# 04_DigitalSensors.net
KiCad netlist of a schematic drawn in Altium Designer
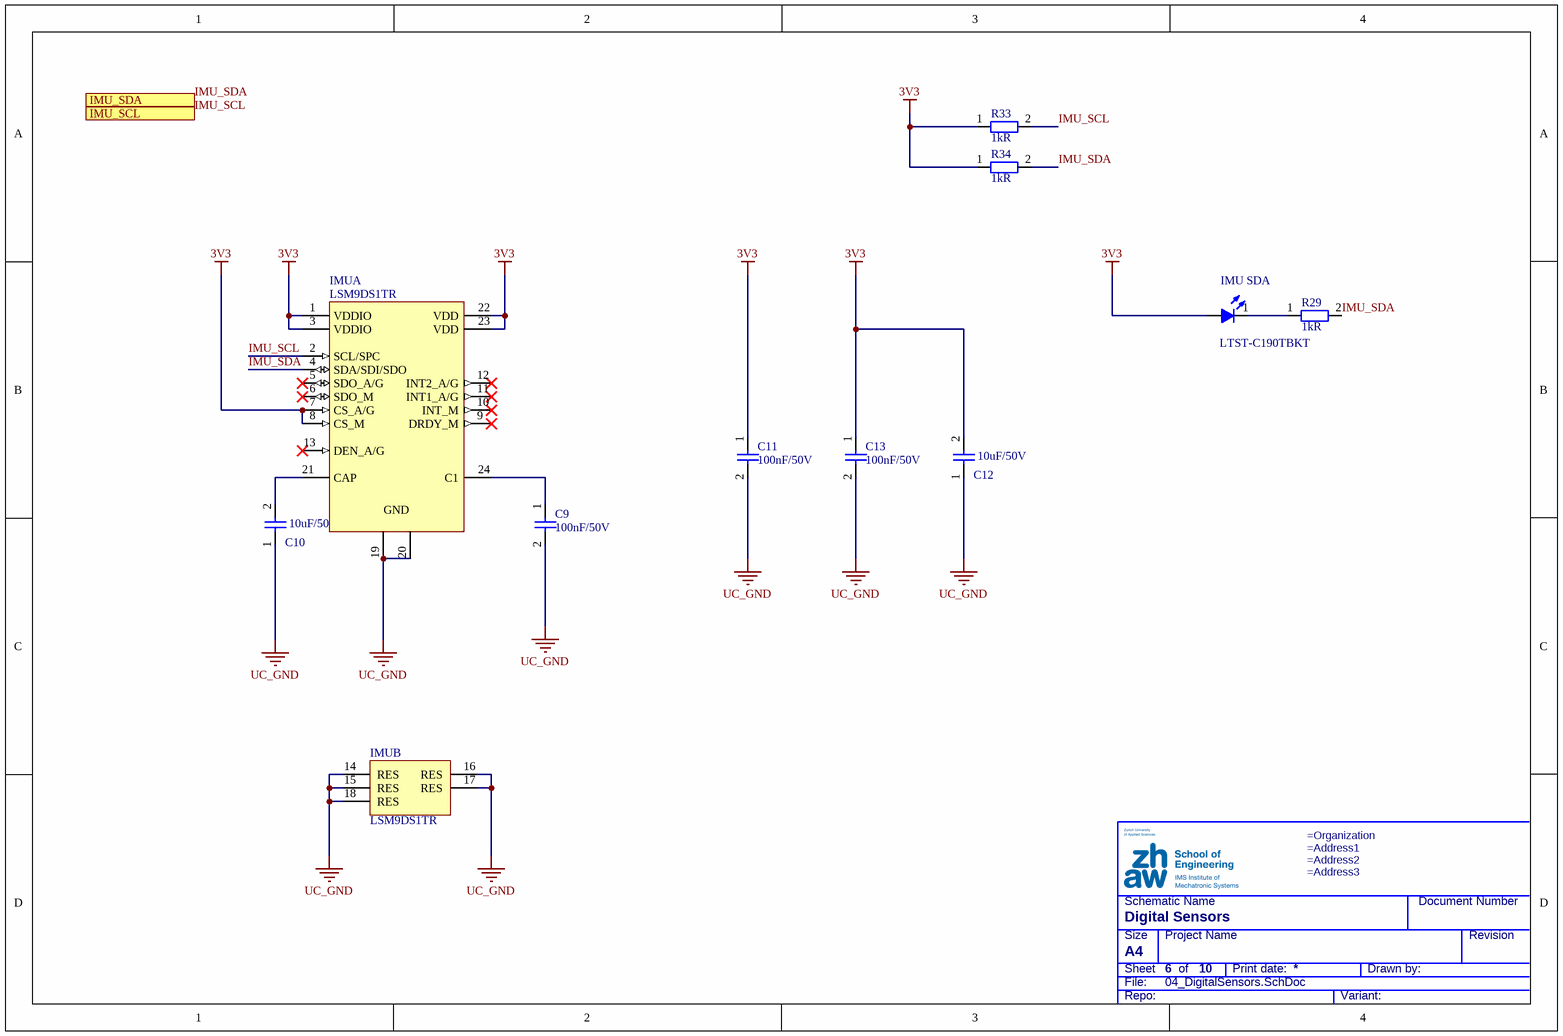
[diagram p0: 04_DigitalSensors.SchDoc]

(export (version "E")
  (design (tool "Eeschema 10.0.6"))
  (components
    (comp (ref "C9")
      (value "100nF/50V")
      (footprint "CAPC1005X05L")
      (description "Cap MLCC, 100nF, 50V, X7R, 10%, 0402")
      (fields (field (name "TOLERANCE") "10%"))
      (libsource (lib "Altium Concord Pro on Altium 365") (part "CAP-NP-2"))
    )
    (comp (ref "C10")
      (value "10uF/50V")
      (footprint "CAPC3216X12L")
      (description "Cap MLCC, 10uF, 50V, X5R, 10%, 1206")
      (fields (field (name "TOLERANCE") "10%"))
      (libsource (lib "Altium Concord Pro on Altium 365") (part "CAP-NP-2"))
    )
    (comp (ref "C11")
      (value "100nF/50V")
      (footprint "CAPC1005X05L")
      (description "Cap MLCC, 100nF, 50V, X7R, 10%, 0402")
      (fields (field (name "TOLERANCE") "10%"))
      (libsource (lib "Altium Concord Pro on Altium 365") (part "CAP-NP-2"))
    )
    (comp (ref "C12")
      (value "10uF/50V")
      (footprint "CAPC3216X12L")
      (description "Cap MLCC, 10uF, 50V, X5R, 10%, 1206")
      (fields (field (name "TOLERANCE") "10%"))
      (libsource (lib "Altium Concord Pro on Altium 365") (part "CAP-NP-2"))
    )
    (comp (ref "C13")
      (value "100nF/50V")
      (footprint "CAPC1005X05L")
      (description "Cap MLCC, 100nF, 50V, X7R, 10%, 0402")
      (fields (field (name "TOLERANCE") "10%"))
      (libsource (lib "Altium Concord Pro on Altium 365") (part "CAP-NP-2"))
    )
    (comp (ref "IMU")
      (value "LSM9DS1TR")
      (footprint "LGA24C43P8X6_350X300X103")
      (description "Gyroscope+Acceleration+Magnetometer, 9-Axis, 1.9..3.6 V, I2C & SPI, LGA-24")
      (libsource (lib "Altium Concord Pro on Altium 365") (part "STM_LSM9DS1TR"))
    )
    (comp (ref "IMU SDA")
      (value "LTST-C190TBKT")
      (footprint "LEDSC160X80X80-2Lbl")
      (description "LED, Blue, 20mA, 2.8V, 0603")
      (libsource (lib "Altium Concord Pro on Altium 365") (part "LED-BLUE-AK-2"))
    )
    (comp (ref "R29")
      (value "1kR")
      (footprint "RESC1005X04L")
      (description "Res, 1kR, 1%, 0.1W, 0402")
      (fields (field (name "POWER") "100mW") (field (name "TOLERANCE") "1%"))
      (libsource (lib "Altium Concord Pro on Altium 365") (part "RES-2"))
    )
    (comp (ref "R33")
      (value "1kR")
      (footprint "RESC1005X04L")
      (description "Res, 1kR, 1%, 0.1W, 0402")
      (fields (field (name "POWER") "100mW") (field (name "TOLERANCE") "1%"))
      (libsource (lib "Altium Concord Pro on Altium 365") (part "RES-2"))
    )
    (comp (ref "R34")
      (value "1kR")
      (footprint "RESC1005X04L")
      (description "Res, 1kR, 1%, 0.1W, 0402")
      (fields (field (name "POWER") "100mW") (field (name "TOLERANCE") "1%"))
      (libsource (lib "Altium Concord Pro on Altium 365") (part "RES-2"))
    )
  )
  (nets
    (net (code "1") (name "/IMU_SCL") (class "Default")
      (node (ref "IMU") (pin "2") (pinfunction "SCL/SPC_2") (pintype "input"))
      (node (ref "R33") (pin "2") (pinfunction "2_2") (pintype "passive"))
    )
    (net (code "2") (name "/IMU_SDA") (class "Default")
      (node (ref "IMU") (pin "4") (pinfunction "SDA/SDI/SDO_4") (pintype "bidirectional"))
      (node (ref "R29") (pin "2") (pinfunction "2_2") (pintype "passive"))
      (node (ref "R34") (pin "2") (pinfunction "2_2") (pintype "passive"))
    )
    (net (code "3") (name "3V3") (class "Default")
      (node (ref "C11") (pin "1") (pinfunction "1_1") (pintype "passive"))
      (node (ref "C12") (pin "2") (pinfunction "2_2") (pintype "passive"))
      (node (ref "C13") (pin "1") (pinfunction "1_1") (pintype "passive"))
      (node (ref "IMU") (pin "1") (pinfunction "VDDIO_1") (pintype "power_in"))
      (node (ref "IMU") (pin "22") (pinfunction "VDD_22") (pintype "power_in"))
      (node (ref "IMU") (pin "23") (pinfunction "VDD_23") (pintype "power_in"))
      (node (ref "IMU") (pin "3") (pinfunction "VDDIO_3") (pintype "power_in"))
      (node (ref "IMU") (pin "7") (pinfunction "CS_A/G_7") (pintype "input"))
      (node (ref "IMU") (pin "8") (pinfunction "CS_M_8") (pintype "input"))
      (node (ref "IMU SDA") (pin "2") (pinfunction "A_2") (pintype "passive"))
      (node (ref "R33") (pin "1") (pinfunction "1_1") (pintype "passive"))
      (node (ref "R34") (pin "1") (pinfunction "1_1") (pintype "passive"))
    )
    (net (code "4") (name "Net-(IMU SDA-K)") (class "Default")
      (node (ref "IMU SDA") (pin "1") (pinfunction "K_1") (pintype "passive"))
      (node (ref "R29") (pin "1") (pinfunction "1_1") (pintype "passive"))
    )
    (net (code "5") (name "Net-(IMUA-C1)") (class "Default")
      (node (ref "C9") (pin "1") (pinfunction "1_1") (pintype "passive"))
      (node (ref "IMU") (pin "24") (pinfunction "C1_24") (pintype "power_in"))
    )
    (net (code "6") (name "Net-(IMUA-CAP)") (class "Default")
      (node (ref "C10") (pin "2") (pinfunction "2_2") (pintype "passive"))
      (node (ref "IMU") (pin "21") (pinfunction "CAP_21") (pintype "power_in"))
    )
    (net (code "7") (name "UC_GND") (class "Default")
      (node (ref "C10") (pin "1") (pinfunction "1_1") (pintype "passive"))
      (node (ref "C11") (pin "2") (pinfunction "2_2") (pintype "passive"))
      (node (ref "C12") (pin "1") (pinfunction "1_1") (pintype "passive"))
      (node (ref "C13") (pin "2") (pinfunction "2_2") (pintype "passive"))
      (node (ref "C9") (pin "2") (pinfunction "2_2") (pintype "passive"))
      (node (ref "IMU") (pin "14") (pinfunction "RES_14") (pintype "passive"))
      (node (ref "IMU") (pin "15") (pinfunction "RES_15") (pintype "passive"))
      (node (ref "IMU") (pin "16") (pinfunction "RES_16") (pintype "passive"))
      (node (ref "IMU") (pin "17") (pinfunction "RES_17") (pintype "passive"))
      (node (ref "IMU") (pin "18") (pinfunction "RES_18") (pintype "passive"))
      (node (ref "IMU") (pin "19") (pinfunction "GND_19") (pintype "power_in"))
      (node (ref "IMU") (pin "20") (pinfunction "GND_20") (pintype "power_in"))
    )
    (net (code "8") (name "unconnected-(IMUA-DEN_A{slash}G-Pad13)") (class "Default")
      (node (ref "IMU") (pin "13") (pinfunction "DEN_A/G_13") (pintype "input+no_connect"))
    )
    (net (code "9") (name "unconnected-(IMUA-DRDY_M-Pad9)") (class "Default")
      (node (ref "IMU") (pin "9") (pinfunction "DRDY_M_9") (pintype "output+no_connect"))
    )
    (net (code "10") (name "unconnected-(IMUA-INT1_A{slash}G-Pad11)") (class "Default")
      (node (ref "IMU") (pin "11") (pinfunction "INT1_A/G_11") (pintype "output+no_connect"))
    )
    (net (code "11") (name "unconnected-(IMUA-INT2_A{slash}G-Pad12)") (class "Default")
      (node (ref "IMU") (pin "12") (pinfunction "INT2_A/G_12") (pintype "output+no_connect"))
    )
    (net (code "12") (name "unconnected-(IMUA-INT_M-Pad10)") (class "Default")
      (node (ref "IMU") (pin "10") (pinfunction "INT_M_10") (pintype "output+no_connect"))
    )
    (net (code "13") (name "unconnected-(IMUA-SDO_A{slash}G-Pad5)") (class "Default")
      (node (ref "IMU") (pin "5") (pinfunction "SDO_A/G_5") (pintype "bidirectional+no_connect"))
    )
    (net (code "14") (name "unconnected-(IMUA-SDO_M-Pad6)") (class "Default")
      (node (ref "IMU") (pin "6") (pinfunction "SDO_M_6") (pintype "bidirectional+no_connect"))
    )
  )
)
